# 06_ZYNQ_POWER.net
KiCad netlist of a schematic drawn in Altium Designer
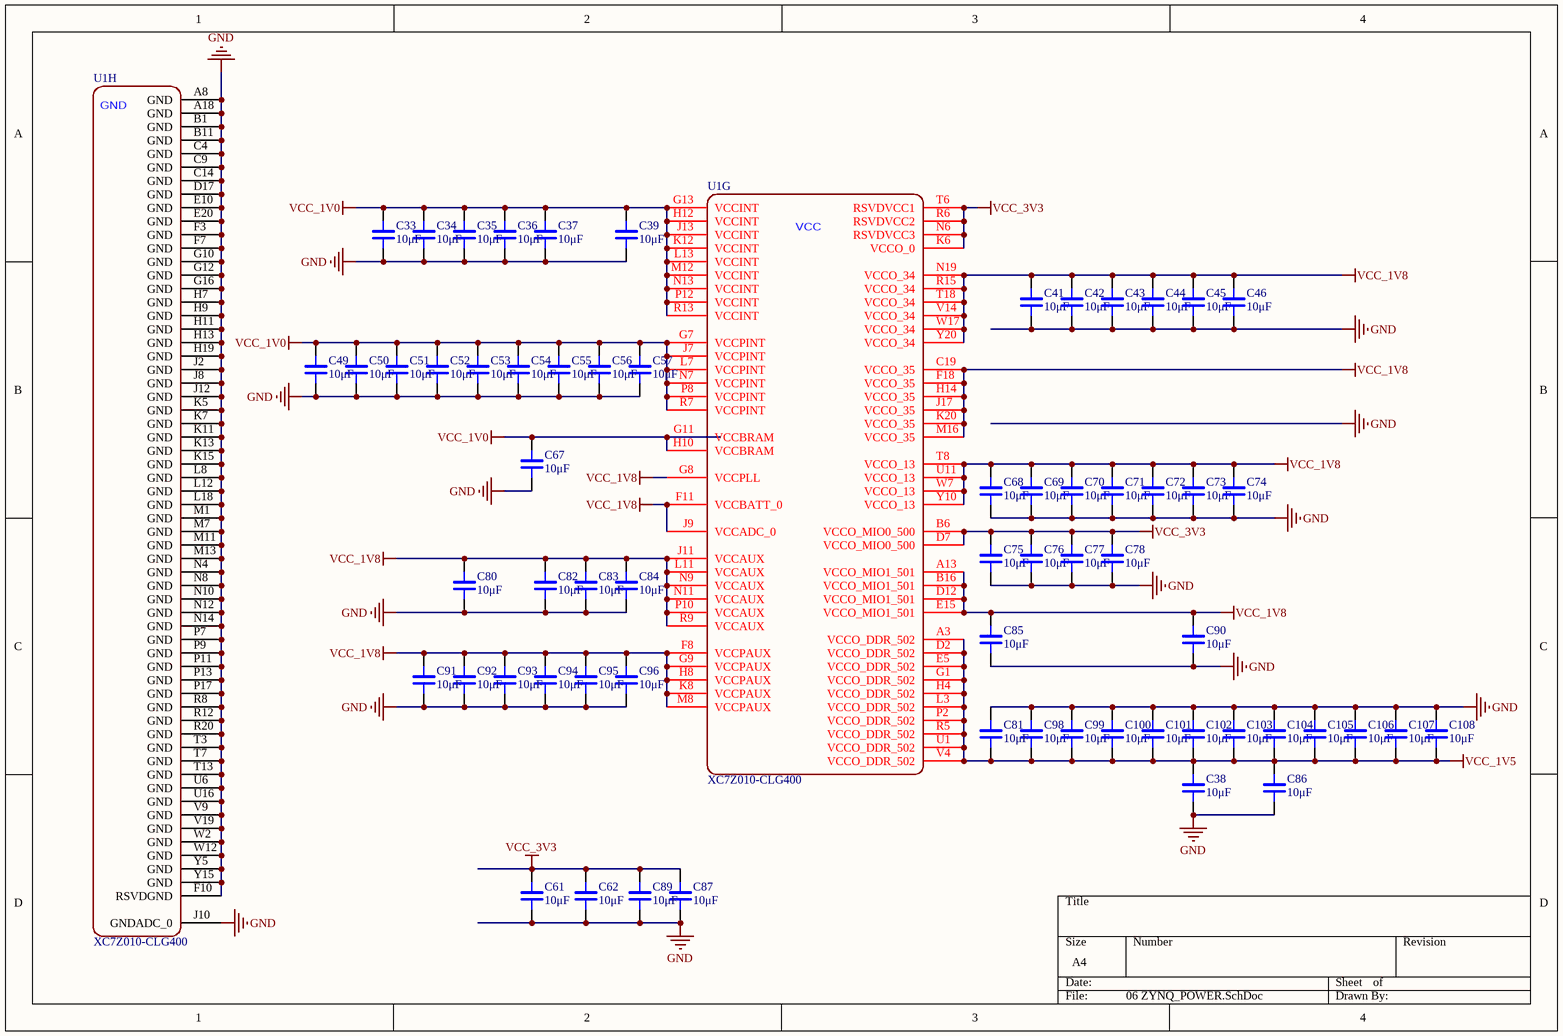
[diagram p0: 06 ZYNQ_POWER.SchDoc]

(export (version "E")
  (design (tool "Eeschema 10.0.6"))
  (components
    (comp (ref "C33")
      (value "10μF")
      (footprint "LC-0402_C")
      (description "Capacitor")
      (libsource (lib "NGFF_M_Key_xc7z010-clg400") (part "CAP_3"))
    )
    (comp (ref "C34")
      (value "10μF")
      (footprint "LC-0402_C")
      (description "Capacitor")
      (libsource (lib "NGFF_M_Key_xc7z010-clg400") (part "CAP_3"))
    )
    (comp (ref "C35")
      (value "10μF")
      (footprint "LC-0402_C")
      (description "Capacitor")
      (libsource (lib "NGFF_M_Key_xc7z010-clg400") (part "CAP_3"))
    )
    (comp (ref "C36")
      (value "10μF")
      (footprint "LC-0402_C")
      (description "Capacitor")
      (libsource (lib "NGFF_M_Key_xc7z010-clg400") (part "CAP_3"))
    )
    (comp (ref "C37")
      (value "10μF")
      (footprint "LC-0402_C")
      (description "Capacitor")
      (libsource (lib "NGFF_M_Key_xc7z010-clg400") (part "CAP_3"))
    )
    (comp (ref "C38")
      (value "10μF")
      (footprint "LC-0402_C")
      (description "Capacitor")
      (libsource (lib "NGFF_M_Key_xc7z010-clg400") (part "CAP_3"))
    )
    (comp (ref "C39")
      (value "10μF")
      (footprint "LC-0402_C")
      (description "Capacitor")
      (libsource (lib "NGFF_M_Key_xc7z010-clg400") (part "CAP_3"))
    )
    (comp (ref "C41")
      (value "10μF")
      (footprint "LC-0402_C")
      (description "Capacitor")
      (libsource (lib "NGFF_M_Key_xc7z010-clg400") (part "CAP_3"))
    )
    (comp (ref "C42")
      (value "10μF")
      (footprint "LC-0402_C")
      (description "Capacitor")
      (libsource (lib "NGFF_M_Key_xc7z010-clg400") (part "CAP_3"))
    )
    (comp (ref "C43")
      (value "10μF")
      (footprint "LC-0402_C")
      (description "Capacitor")
      (libsource (lib "NGFF_M_Key_xc7z010-clg400") (part "CAP_3"))
    )
    (comp (ref "C44")
      (value "10μF")
      (footprint "LC-0402_C")
      (description "Capacitor")
      (libsource (lib "NGFF_M_Key_xc7z010-clg400") (part "CAP_3"))
    )
    (comp (ref "C45")
      (value "10μF")
      (footprint "LC-0402_C")
      (description "Capacitor")
      (libsource (lib "NGFF_M_Key_xc7z010-clg400") (part "CAP_3"))
    )
    (comp (ref "C46")
      (value "10μF")
      (footprint "LC-0402_C")
      (description "Capacitor")
      (libsource (lib "NGFF_M_Key_xc7z010-clg400") (part "CAP_3"))
    )
    (comp (ref "C49")
      (value "10μF")
      (footprint "LC-0402_C")
      (description "Capacitor")
      (libsource (lib "NGFF_M_Key_xc7z010-clg400") (part "CAP_3"))
    )
    (comp (ref "C50")
      (value "10μF")
      (footprint "LC-0402_C")
      (description "Capacitor")
      (libsource (lib "NGFF_M_Key_xc7z010-clg400") (part "CAP_3"))
    )
    (comp (ref "C51")
      (value "10μF")
      (footprint "LC-0402_C")
      (description "Capacitor")
      (libsource (lib "NGFF_M_Key_xc7z010-clg400") (part "CAP_3"))
    )
    (comp (ref "C52")
      (value "10μF")
      (footprint "LC-0402_C")
      (description "Capacitor")
      (libsource (lib "NGFF_M_Key_xc7z010-clg400") (part "CAP_3"))
    )
    (comp (ref "C53")
      (value "10μF")
      (footprint "LC-0402_C")
      (description "Capacitor")
      (libsource (lib "NGFF_M_Key_xc7z010-clg400") (part "CAP_3"))
    )
    (comp (ref "C54")
      (value "10μF")
      (footprint "LC-0402_C")
      (description "Capacitor")
      (libsource (lib "NGFF_M_Key_xc7z010-clg400") (part "CAP_3"))
    )
    (comp (ref "C55")
      (value "10μF")
      (footprint "LC-0402_C")
      (description "Capacitor")
      (libsource (lib "NGFF_M_Key_xc7z010-clg400") (part "CAP_3"))
    )
    (comp (ref "C56")
      (value "10μF")
      (footprint "LC-0402_C")
      (description "Capacitor")
      (libsource (lib "NGFF_M_Key_xc7z010-clg400") (part "CAP_3"))
    )
    (comp (ref "C57")
      (value "10μF")
      (footprint "LC-0402_C")
      (description "Capacitor")
      (libsource (lib "NGFF_M_Key_xc7z010-clg400") (part "CAP_3"))
    )
    (comp (ref "C61")
      (value "10μF")
      (footprint "LC-0402_C")
      (description "Capacitor")
      (libsource (lib "NGFF_M_Key_xc7z010-clg400") (part "CAP_3"))
    )
    (comp (ref "C62")
      (value "10μF")
      (footprint "LC-0402_C")
      (description "Capacitor")
      (libsource (lib "NGFF_M_Key_xc7z010-clg400") (part "CAP_3"))
    )
    (comp (ref "C67")
      (value "10μF")
      (footprint "LC-0402_C")
      (description "Capacitor")
      (libsource (lib "NGFF_M_Key_xc7z010-clg400") (part "CAP_3"))
    )
    (comp (ref "C68")
      (value "10μF")
      (footprint "LC-0402_C")
      (description "Capacitor")
      (libsource (lib "NGFF_M_Key_xc7z010-clg400") (part "CAP_3"))
    )
    (comp (ref "C69")
      (value "10μF")
      (footprint "LC-0402_C")
      (description "Capacitor")
      (libsource (lib "NGFF_M_Key_xc7z010-clg400") (part "CAP_3"))
    )
    (comp (ref "C70")
      (value "10μF")
      (footprint "LC-0402_C")
      (description "Capacitor")
      (libsource (lib "NGFF_M_Key_xc7z010-clg400") (part "CAP_3"))
    )
    (comp (ref "C71")
      (value "10μF")
      (footprint "LC-0402_C")
      (description "Capacitor")
      (libsource (lib "NGFF_M_Key_xc7z010-clg400") (part "CAP_3"))
    )
    (comp (ref "C72")
      (value "10μF")
      (footprint "LC-0402_C")
      (description "Capacitor")
      (libsource (lib "NGFF_M_Key_xc7z010-clg400") (part "CAP_3"))
    )
    (comp (ref "C73")
      (value "10μF")
      (footprint "LC-0402_C")
      (description "Capacitor")
      (libsource (lib "NGFF_M_Key_xc7z010-clg400") (part "CAP_3"))
    )
    (comp (ref "C74")
      (value "10μF")
      (footprint "LC-0402_C")
      (description "Capacitor")
      (libsource (lib "NGFF_M_Key_xc7z010-clg400") (part "CAP_3"))
    )
    (comp (ref "C75")
      (value "10μF")
      (footprint "LC-0402_C")
      (description "Capacitor")
      (libsource (lib "NGFF_M_Key_xc7z010-clg400") (part "CAP_3"))
    )
    (comp (ref "C76")
      (value "10μF")
      (footprint "LC-0402_C")
      (description "Capacitor")
      (libsource (lib "NGFF_M_Key_xc7z010-clg400") (part "CAP_3"))
    )
    (comp (ref "C77")
      (value "10μF")
      (footprint "LC-0402_C")
      (description "Capacitor")
      (libsource (lib "NGFF_M_Key_xc7z010-clg400") (part "CAP_3"))
    )
    (comp (ref "C78")
      (value "10μF")
      (footprint "LC-0402_C")
      (description "Capacitor")
      (libsource (lib "NGFF_M_Key_xc7z010-clg400") (part "CAP_3"))
    )
    (comp (ref "C80")
      (value "10μF")
      (footprint "LC-0402_C")
      (description "Capacitor")
      (libsource (lib "NGFF_M_Key_xc7z010-clg400") (part "CAP_3"))
    )
    (comp (ref "C81")
      (value "10μF")
      (footprint "LC-0402_C")
      (description "Capacitor")
      (libsource (lib "NGFF_M_Key_xc7z010-clg400") (part "CAP_3"))
    )
    (comp (ref "C82")
      (value "10μF")
      (footprint "LC-0402_C")
      (description "Capacitor")
      (libsource (lib "NGFF_M_Key_xc7z010-clg400") (part "CAP_3"))
    )
    (comp (ref "C83")
      (value "10μF")
      (footprint "LC-0402_C")
      (description "Capacitor")
      (libsource (lib "NGFF_M_Key_xc7z010-clg400") (part "CAP_3"))
    )
    (comp (ref "C84")
      (value "10μF")
      (footprint "LC-0402_C")
      (description "Capacitor")
      (libsource (lib "NGFF_M_Key_xc7z010-clg400") (part "CAP_3"))
    )
    (comp (ref "C85")
      (value "10μF")
      (footprint "LC-0402_C")
      (description "Capacitor")
      (libsource (lib "NGFF_M_Key_xc7z010-clg400") (part "CAP_3"))
    )
    (comp (ref "C86")
      (value "10μF")
      (footprint "LC-0402_C")
      (description "Capacitor")
      (libsource (lib "NGFF_M_Key_xc7z010-clg400") (part "CAP_3"))
    )
    (comp (ref "C87")
      (value "10μF")
      (footprint "LC-0402_C")
      (description "Capacitor")
      (libsource (lib "NGFF_M_Key_xc7z010-clg400") (part "CAP_3"))
    )
    (comp (ref "C89")
      (value "10μF")
      (footprint "LC-0402_C")
      (description "Capacitor")
      (libsource (lib "NGFF_M_Key_xc7z010-clg400") (part "CAP_3"))
    )
    (comp (ref "C90")
      (value "10μF")
      (footprint "LC-0402_C")
      (description "Capacitor")
      (libsource (lib "NGFF_M_Key_xc7z010-clg400") (part "CAP_3"))
    )
    (comp (ref "C91")
      (value "10μF")
      (footprint "LC-0402_C")
      (description "Capacitor")
      (libsource (lib "NGFF_M_Key_xc7z010-clg400") (part "CAP_3"))
    )
    (comp (ref "C92")
      (value "10μF")
      (footprint "LC-0402_C")
      (description "Capacitor")
      (libsource (lib "NGFF_M_Key_xc7z010-clg400") (part "CAP_3"))
    )
    (comp (ref "C93")
      (value "10μF")
      (footprint "LC-0402_C")
      (description "Capacitor")
      (libsource (lib "NGFF_M_Key_xc7z010-clg400") (part "CAP_3"))
    )
    (comp (ref "C94")
      (value "10μF")
      (footprint "LC-0402_C")
      (description "Capacitor")
      (libsource (lib "NGFF_M_Key_xc7z010-clg400") (part "CAP_3"))
    )
    (comp (ref "C95")
      (value "10μF")
      (footprint "LC-0402_C")
      (description "Capacitor")
      (libsource (lib "NGFF_M_Key_xc7z010-clg400") (part "CAP_3"))
    )
    (comp (ref "C96")
      (value "10μF")
      (footprint "LC-0402_C")
      (description "Capacitor")
      (libsource (lib "NGFF_M_Key_xc7z010-clg400") (part "CAP_3"))
    )
    (comp (ref "C98")
      (value "10μF")
      (footprint "LC-0402_C")
      (description "Capacitor")
      (libsource (lib "NGFF_M_Key_xc7z010-clg400") (part "CAP_3"))
    )
    (comp (ref "C99")
      (value "10μF")
      (footprint "LC-0402_C")
      (description "Capacitor")
      (libsource (lib "NGFF_M_Key_xc7z010-clg400") (part "CAP_3"))
    )
    (comp (ref "C100")
      (value "10μF")
      (footprint "LC-0402_C")
      (description "Capacitor")
      (libsource (lib "NGFF_M_Key_xc7z010-clg400") (part "CAP_3"))
    )
    (comp (ref "C101")
      (value "10μF")
      (footprint "LC-0402_C")
      (description "Capacitor")
      (libsource (lib "NGFF_M_Key_xc7z010-clg400") (part "CAP_3"))
    )
    (comp (ref "C102")
      (value "10μF")
      (footprint "LC-0402_C")
      (description "Capacitor")
      (libsource (lib "NGFF_M_Key_xc7z010-clg400") (part "CAP_3"))
    )
    (comp (ref "C103")
      (value "10μF")
      (footprint "LC-0402_C")
      (description "Capacitor")
      (libsource (lib "NGFF_M_Key_xc7z010-clg400") (part "CAP_3"))
    )
    (comp (ref "C104")
      (value "10μF")
      (footprint "LC-0402_C")
      (description "Capacitor")
      (libsource (lib "NGFF_M_Key_xc7z010-clg400") (part "CAP_3"))
    )
    (comp (ref "C105")
      (value "10μF")
      (footprint "LC-0402_C")
      (description "Capacitor")
      (libsource (lib "NGFF_M_Key_xc7z010-clg400") (part "CAP_3"))
    )
    (comp (ref "C106")
      (value "10μF")
      (footprint "LC-0402_C")
      (description "Capacitor")
      (libsource (lib "NGFF_M_Key_xc7z010-clg400") (part "CAP_3"))
    )
    (comp (ref "C107")
      (value "10μF")
      (footprint "LC-0402_C")
      (description "Capacitor")
      (libsource (lib "NGFF_M_Key_xc7z010-clg400") (part "CAP_3"))
    )
    (comp (ref "C108")
      (value "10μF")
      (footprint "LC-0402_C")
      (description "Capacitor")
      (libsource (lib "NGFF_M_Key_xc7z010-clg400") (part "CAP_3"))
    )
    (comp (ref "U1")
      (value "XC7Z010-CLG400")
      (footprint "CLG400-0.8")
      (libsource (lib "DDR3_xc7z010-clg400") (part "XC7Z010-CLG400"))
    )
  )
  (nets
    (net (code "1") (name "GND") (class "Default")
      (node (ref "C100") (pin "2") (pinfunction "2_2") (pintype "passive"))
      (node (ref "C101") (pin "2") (pinfunction "2_2") (pintype "passive"))
      (node (ref "C102") (pin "2") (pinfunction "2_2") (pintype "passive"))
      (node (ref "C103") (pin "2") (pinfunction "2_2") (pintype "passive"))
      (node (ref "C104") (pin "2") (pinfunction "2_2") (pintype "passive"))
      (node (ref "C105") (pin "2") (pinfunction "2_2") (pintype "passive"))
      (node (ref "C106") (pin "2") (pinfunction "2_2") (pintype "passive"))
      (node (ref "C107") (pin "2") (pinfunction "2_2") (pintype "passive"))
      (node (ref "C108") (pin "2") (pinfunction "2_2") (pintype "passive"))
      (node (ref "C33") (pin "1") (pinfunction "1_1") (pintype "passive"))
      (node (ref "C34") (pin "1") (pinfunction "1_1") (pintype "passive"))
      (node (ref "C35") (pin "1") (pinfunction "1_1") (pintype "passive"))
      (node (ref "C36") (pin "1") (pinfunction "1_1") (pintype "passive"))
      (node (ref "C37") (pin "1") (pinfunction "1_1") (pintype "passive"))
      (node (ref "C38") (pin "1") (pinfunction "1_1") (pintype "passive"))
      (node (ref "C39") (pin "1") (pinfunction "1_1") (pintype "passive"))
      (node (ref "C41") (pin "1") (pinfunction "1_1") (pintype "passive"))
      (node (ref "C42") (pin "1") (pinfunction "1_1") (pintype "passive"))
      (node (ref "C43") (pin "1") (pinfunction "1_1") (pintype "passive"))
      (node (ref "C44") (pin "1") (pinfunction "1_1") (pintype "passive"))
      (node (ref "C45") (pin "1") (pinfunction "1_1") (pintype "passive"))
      (node (ref "C46") (pin "1") (pinfunction "1_1") (pintype "passive"))
      (node (ref "C49") (pin "1") (pinfunction "1_1") (pintype "passive"))
      (node (ref "C50") (pin "1") (pinfunction "1_1") (pintype "passive"))
      (node (ref "C51") (pin "1") (pinfunction "1_1") (pintype "passive"))
      (node (ref "C52") (pin "1") (pinfunction "1_1") (pintype "passive"))
      (node (ref "C53") (pin "1") (pinfunction "1_1") (pintype "passive"))
      (node (ref "C54") (pin "1") (pinfunction "1_1") (pintype "passive"))
      (node (ref "C55") (pin "1") (pinfunction "1_1") (pintype "passive"))
      (node (ref "C56") (pin "1") (pinfunction "1_1") (pintype "passive"))
      (node (ref "C57") (pin "1") (pinfunction "1_1") (pintype "passive"))
      (node (ref "C61") (pin "1") (pinfunction "1_1") (pintype "passive"))
      (node (ref "C62") (pin "1") (pinfunction "1_1") (pintype "passive"))
      (node (ref "C67") (pin "1") (pinfunction "1_1") (pintype "passive"))
      (node (ref "C68") (pin "1") (pinfunction "1_1") (pintype "passive"))
      (node (ref "C69") (pin "1") (pinfunction "1_1") (pintype "passive"))
      (node (ref "C70") (pin "1") (pinfunction "1_1") (pintype "passive"))
      (node (ref "C71") (pin "1") (pinfunction "1_1") (pintype "passive"))
      (node (ref "C72") (pin "1") (pinfunction "1_1") (pintype "passive"))
      (node (ref "C73") (pin "1") (pinfunction "1_1") (pintype "passive"))
      (node (ref "C74") (pin "1") (pinfunction "1_1") (pintype "passive"))
      (node (ref "C75") (pin "1") (pinfunction "1_1") (pintype "passive"))
      (node (ref "C76") (pin "1") (pinfunction "1_1") (pintype "passive"))
      (node (ref "C77") (pin "1") (pinfunction "1_1") (pintype "passive"))
      (node (ref "C78") (pin "1") (pinfunction "1_1") (pintype "passive"))
      (node (ref "C80") (pin "1") (pinfunction "1_1") (pintype "passive"))
      (node (ref "C81") (pin "2") (pinfunction "2_2") (pintype "passive"))
      (node (ref "C82") (pin "1") (pinfunction "1_1") (pintype "passive"))
      (node (ref "C83") (pin "1") (pinfunction "1_1") (pintype "passive"))
      (node (ref "C84") (pin "1") (pinfunction "1_1") (pintype "passive"))
      (node (ref "C85") (pin "1") (pinfunction "1_1") (pintype "passive"))
      (node (ref "C86") (pin "1") (pinfunction "1_1") (pintype "passive"))
      (node (ref "C87") (pin "1") (pinfunction "1_1") (pintype "passive"))
      (node (ref "C89") (pin "1") (pinfunction "1_1") (pintype "passive"))
      (node (ref "C90") (pin "1") (pinfunction "1_1") (pintype "passive"))
      (node (ref "C91") (pin "1") (pinfunction "1_1") (pintype "passive"))
      (node (ref "C92") (pin "1") (pinfunction "1_1") (pintype "passive"))
      (node (ref "C93") (pin "1") (pinfunction "1_1") (pintype "passive"))
      (node (ref "C94") (pin "1") (pinfunction "1_1") (pintype "passive"))
      (node (ref "C95") (pin "1") (pinfunction "1_1") (pintype "passive"))
      (node (ref "C96") (pin "1") (pinfunction "1_1") (pintype "passive"))
      (node (ref "C98") (pin "2") (pinfunction "2_2") (pintype "passive"))
      (node (ref "C99") (pin "2") (pinfunction "2_2") (pintype "passive"))
      (node (ref "U1") (pin "A18") (pinfunction "GND_A18") (pintype "passive"))
      (node (ref "U1") (pin "A8") (pinfunction "GND_A8") (pintype "passive"))
      (node (ref "U1") (pin "B1") (pinfunction "GND_B1") (pintype "passive"))
      (node (ref "U1") (pin "B11") (pinfunction "GND_B11") (pintype "passive"))
      (node (ref "U1") (pin "C14") (pinfunction "GND_C14") (pintype "passive"))
      (node (ref "U1") (pin "C4") (pinfunction "GND_C4") (pintype "passive"))
      (node (ref "U1") (pin "C9") (pinfunction "GND_C9") (pintype "passive"))
      (node (ref "U1") (pin "D17") (pinfunction "GND_D17") (pintype "passive"))
      (node (ref "U1") (pin "E10") (pinfunction "GND_E10") (pintype "passive"))
      (node (ref "U1") (pin "E20") (pinfunction "GND_E20") (pintype "passive"))
      (node (ref "U1") (pin "F10") (pinfunction "RSVDGND_F10") (pintype "passive"))
      (node (ref "U1") (pin "F3") (pinfunction "GND_F3") (pintype "passive"))
      (node (ref "U1") (pin "F7") (pinfunction "GND_F7") (pintype "passive"))
      (node (ref "U1") (pin "G10") (pinfunction "GND_G10") (pintype "passive"))
      (node (ref "U1") (pin "G12") (pinfunction "GND_G12") (pintype "passive"))
      (node (ref "U1") (pin "G16") (pinfunction "GND_G16") (pintype "passive"))
      (node (ref "U1") (pin "H11") (pinfunction "GND_H11") (pintype "passive"))
      (node (ref "U1") (pin "H13") (pinfunction "GND_H13") (pintype "passive"))
      (node (ref "U1") (pin "H19") (pinfunction "GND_H19") (pintype "passive"))
      (node (ref "U1") (pin "H7") (pinfunction "GND_H7") (pintype "passive"))
      (node (ref "U1") (pin "H9") (pinfunction "GND_H9") (pintype "passive"))
      (node (ref "U1") (pin "J10") (pinfunction "GNDADC_0_J10") (pintype "passive"))
      (node (ref "U1") (pin "J12") (pinfunction "GND_J12") (pintype "passive"))
      (node (ref "U1") (pin "J2") (pinfunction "GND_J2") (pintype "passive"))
      (node (ref "U1") (pin "J8") (pinfunction "GND_J8") (pintype "passive"))
      (node (ref "U1") (pin "K11") (pinfunction "GND_K11") (pintype "passive"))
      (node (ref "U1") (pin "K13") (pinfunction "GND_K13") (pintype "passive"))
      (node (ref "U1") (pin "K15") (pinfunction "GND_K15") (pintype "passive"))
      (node (ref "U1") (pin "K5") (pinfunction "GND_K5") (pintype "passive"))
      (node (ref "U1") (pin "K7") (pinfunction "GND_K7") (pintype "passive"))
      (node (ref "U1") (pin "L12") (pinfunction "GND_L12") (pintype "passive"))
      (node (ref "U1") (pin "L18") (pinfunction "GND_L18") (pintype "passive"))
      (node (ref "U1") (pin "L8") (pinfunction "GND_L8") (pintype "passive"))
      (node (ref "U1") (pin "M1") (pinfunction "GND_M1") (pintype "passive"))
      (node (ref "U1") (pin "M11") (pinfunction "GND_M11") (pintype "passive"))
      (node (ref "U1") (pin "M13") (pinfunction "GND_M13") (pintype "passive"))
      (node (ref "U1") (pin "M7") (pinfunction "GND_M7") (pintype "passive"))
      (node (ref "U1") (pin "N10") (pinfunction "GND_N10") (pintype "passive"))
      (node (ref "U1") (pin "N12") (pinfunction "GND_N12") (pintype "passive"))
      (node (ref "U1") (pin "N14") (pinfunction "GND_N14") (pintype "passive"))
      (node (ref "U1") (pin "N4") (pinfunction "GND_N4") (pintype "passive"))
      (node (ref "U1") (pin "N8") (pinfunction "GND_N8") (pintype "passive"))
      (node (ref "U1") (pin "P11") (pinfunction "GND_P11") (pintype "passive"))
      (node (ref "U1") (pin "P13") (pinfunction "GND_P13") (pintype "passive"))
      (node (ref "U1") (pin "P17") (pinfunction "GND_P17") (pintype "passive"))
      (node (ref "U1") (pin "P7") (pinfunction "GND_P7") (pintype "passive"))
      (node (ref "U1") (pin "P9") (pinfunction "GND_P9") (pintype "passive"))
      (node (ref "U1") (pin "R12") (pinfunction "GND_R12") (pintype "passive"))
      (node (ref "U1") (pin "R20") (pinfunction "GND_R20") (pintype "passive"))
      (node (ref "U1") (pin "R8") (pinfunction "GND_R8") (pintype "passive"))
      (node (ref "U1") (pin "T13") (pinfunction "GND_T13") (pintype "passive"))
      (node (ref "U1") (pin "T3") (pinfunction "GND_T3") (pintype "passive"))
      (node (ref "U1") (pin "T7") (pinfunction "GND_T7") (pintype "passive"))
      (node (ref "U1") (pin "U16") (pinfunction "GND_U16") (pintype "passive"))
      (node (ref "U1") (pin "U6") (pinfunction "GND_U6") (pintype "passive"))
      (node (ref "U1") (pin "V19") (pinfunction "GND_V19") (pintype "passive"))
      (node (ref "U1") (pin "V9") (pinfunction "GND_V9") (pintype "passive"))
      (node (ref "U1") (pin "W12") (pinfunction "GND_W12") (pintype "passive"))
      (node (ref "U1") (pin "W2") (pinfunction "GND_W2") (pintype "passive"))
      (node (ref "U1") (pin "Y15") (pinfunction "GND_Y15") (pintype "passive"))
      (node (ref "U1") (pin "Y5") (pinfunction "GND_Y5") (pintype "passive"))
    )
    (net (code "2") (name "VCC_1V0") (class "Default")
      (node (ref "C33") (pin "2") (pinfunction "2_2") (pintype "passive"))
      (node (ref "C34") (pin "2") (pinfunction "2_2") (pintype "passive"))
      (node (ref "C35") (pin "2") (pinfunction "2_2") (pintype "passive"))
      (node (ref "C36") (pin "2") (pinfunction "2_2") (pintype "passive"))
      (node (ref "C37") (pin "2") (pinfunction "2_2") (pintype "passive"))
      (node (ref "C39") (pin "2") (pinfunction "2_2") (pintype "passive"))
      (node (ref "C49") (pin "2") (pinfunction "2_2") (pintype "passive"))
      (node (ref "C50") (pin "2") (pinfunction "2_2") (pintype "passive"))
      (node (ref "C51") (pin "2") (pinfunction "2_2") (pintype "passive"))
      (node (ref "C52") (pin "2") (pinfunction "2_2") (pintype "passive"))
      (node (ref "C53") (pin "2") (pinfunction "2_2") (pintype "passive"))
      (node (ref "C54") (pin "2") (pinfunction "2_2") (pintype "passive"))
      (node (ref "C55") (pin "2") (pinfunction "2_2") (pintype "passive"))
      (node (ref "C56") (pin "2") (pinfunction "2_2") (pintype "passive"))
      (node (ref "C57") (pin "2") (pinfunction "2_2") (pintype "passive"))
      (node (ref "C67") (pin "2") (pinfunction "2_2") (pintype "passive"))
      (node (ref "U1") (pin "G11") (pinfunction "VCCBRAM_G11") (pintype "passive"))
      (node (ref "U1") (pin "G13") (pinfunction "VCCINT_G13") (pintype "passive"))
      (node (ref "U1") (pin "G7") (pinfunction "VCCPINT_G7") (pintype "passive"))
      (node (ref "U1") (pin "H10") (pinfunction "VCCBRAM_H10") (pintype "passive"))
      (node (ref "U1") (pin "H12") (pinfunction "VCCINT_H12") (pintype "passive"))
      (node (ref "U1") (pin "J13") (pinfunction "VCCINT_J13") (pintype "passive"))
      (node (ref "U1") (pin "J7") (pinfunction "VCCPINT_J7") (pintype "passive"))
      (node (ref "U1") (pin "K12") (pinfunction "VCCINT_K12") (pintype "passive"))
      (node (ref "U1") (pin "L13") (pinfunction "VCCINT_L13") (pintype "passive"))
      (node (ref "U1") (pin "L7") (pinfunction "VCCPINT_L7") (pintype "passive"))
      (node (ref "U1") (pin "M12") (pinfunction "VCCINT_M12") (pintype "passive"))
      (node (ref "U1") (pin "N13") (pinfunction "VCCINT_N13") (pintype "passive"))
      (node (ref "U1") (pin "N7") (pinfunction "VCCPINT_N7") (pintype "passive"))
      (node (ref "U1") (pin "P12") (pinfunction "VCCINT_P12") (pintype "passive"))
      (node (ref "U1") (pin "P8") (pinfunction "VCCPINT_P8") (pintype "passive"))
      (node (ref "U1") (pin "R13") (pinfunction "VCCINT_R13") (pintype "passive"))
      (node (ref "U1") (pin "R7") (pinfunction "VCCPINT_R7") (pintype "passive"))
    )
    (net (code "3") (name "VCC_1V5") (class "Default")
      (node (ref "C100") (pin "1") (pinfunction "1_1") (pintype "passive"))
      (node (ref "C101") (pin "1") (pinfunction "1_1") (pintype "passive"))
      (node (ref "C102") (pin "1") (pinfunction "1_1") (pintype "passive"))
      (node (ref "C103") (pin "1") (pinfunction "1_1") (pintype "passive"))
      (node (ref "C104") (pin "1") (pinfunction "1_1") (pintype "passive"))
      (node (ref "C105") (pin "1") (pinfunction "1_1") (pintype "passive"))
      (node (ref "C106") (pin "1") (pinfunction "1_1") (pintype "passive"))
      (node (ref "C107") (pin "1") (pinfunction "1_1") (pintype "passive"))
      (node (ref "C108") (pin "1") (pinfunction "1_1") (pintype "passive"))
      (node (ref "C38") (pin "2") (pinfunction "2_2") (pintype "passive"))
      (node (ref "C81") (pin "1") (pinfunction "1_1") (pintype "passive"))
      (node (ref "C86") (pin "2") (pinfunction "2_2") (pintype "passive"))
      (node (ref "C98") (pin "1") (pinfunction "1_1") (pintype "passive"))
      (node (ref "C99") (pin "1") (pinfunction "1_1") (pintype "passive"))
      (node (ref "U1") (pin "A3") (pinfunction "VCCO_DDR_502_A3") (pintype "passive"))
      (node (ref "U1") (pin "D2") (pinfunction "VCCO_DDR_502_D2") (pintype "passive"))
      (node (ref "U1") (pin "E5") (pinfunction "VCCO_DDR_502_E5") (pintype "passive"))
      (node (ref "U1") (pin "G1") (pinfunction "VCCO_DDR_502_G1") (pintype "passive"))
      (node (ref "U1") (pin "H4") (pinfunction "VCCO_DDR_502_H4") (pintype "passive"))
      (node (ref "U1") (pin "L3") (pinfunction "VCCO_DDR_502_L3") (pintype "passive"))
      (node (ref "U1") (pin "P2") (pinfunction "VCCO_DDR_502_P2") (pintype "passive"))
      (node (ref "U1") (pin "R5") (pinfunction "VCCO_DDR_502_R5") (pintype "passive"))
      (node (ref "U1") (pin "U1") (pinfunction "VCCO_DDR_502_U1") (pintype "passive"))
      (node (ref "U1") (pin "V4") (pinfunction "VCCO_DDR_502_V4") (pintype "passive"))
    )
    (net (code "4") (name "VCC_1V8") (class "Default")
      (node (ref "C41") (pin "2") (pinfunction "2_2") (pintype "passive"))
      (node (ref "C42") (pin "2") (pinfunction "2_2") (pintype "passive"))
      (node (ref "C43") (pin "2") (pinfunction "2_2") (pintype "passive"))
      (node (ref "C44") (pin "2") (pinfunction "2_2") (pintype "passive"))
      (node (ref "C45") (pin "2") (pinfunction "2_2") (pintype "passive"))
      (node (ref "C46") (pin "2") (pinfunction "2_2") (pintype "passive"))
      (node (ref "C68") (pin "2") (pinfunction "2_2") (pintype "passive"))
      (node (ref "C69") (pin "2") (pinfunction "2_2") (pintype "passive"))
      (node (ref "C70") (pin "2") (pinfunction "2_2") (pintype "passive"))
      (node (ref "C71") (pin "2") (pinfunction "2_2") (pintype "passive"))
      (node (ref "C72") (pin "2") (pinfunction "2_2") (pintype "passive"))
      (node (ref "C73") (pin "2") (pinfunction "2_2") (pintype "passive"))
      (node (ref "C74") (pin "2") (pinfunction "2_2") (pintype "passive"))
      (node (ref "C80") (pin "2") (pinfunction "2_2") (pintype "passive"))
      (node (ref "C82") (pin "2") (pinfunction "2_2") (pintype "passive"))
      (node (ref "C83") (pin "2") (pinfunction "2_2") (pintype "passive"))
      (node (ref "C84") (pin "2") (pinfunction "2_2") (pintype "passive"))
      (node (ref "C85") (pin "2") (pinfunction "2_2") (pintype "passive"))
      (node (ref "C90") (pin "2") (pinfunction "2_2") (pintype "passive"))
      (node (ref "C91") (pin "2") (pinfunction "2_2") (pintype "passive"))
      (node (ref "C92") (pin "2") (pinfunction "2_2") (pintype "passive"))
      (node (ref "C93") (pin "2") (pinfunction "2_2") (pintype "passive"))
      (node (ref "C94") (pin "2") (pinfunction "2_2") (pintype "passive"))
      (node (ref "C95") (pin "2") (pinfunction "2_2") (pintype "passive"))
      (node (ref "C96") (pin "2") (pinfunction "2_2") (pintype "passive"))
      (node (ref "U1") (pin "A13") (pinfunction "VCCO_MIO1_501_A13") (pintype "passive"))
      (node (ref "U1") (pin "B16") (pinfunction "VCCO_MIO1_501_B16") (pintype "passive"))
      (node (ref "U1") (pin "C19") (pinfunction "VCCO_35_C19") (pintype "passive"))
      (node (ref "U1") (pin "D12") (pinfunction "VCCO_MIO1_501_D12") (pintype "passive"))
      (node (ref "U1") (pin "E15") (pinfunction "VCCO_MIO1_501_E15") (pintype "passive"))
      (node (ref "U1") (pin "F11") (pinfunction "VCCBATT_0_F11") (pintype "passive"))
      (node (ref "U1") (pin "F18") (pinfunction "VCCO_35_F18") (pintype "passive"))
      (node (ref "U1") (pin "F8") (pinfunction "VCCPAUX_F8") (pintype "passive"))
      (node (ref "U1") (pin "G8") (pinfunction "VCCPLL_G8") (pintype "passive"))
      (node (ref "U1") (pin "G9") (pinfunction "VCCPAUX_G9") (pintype "passive"))
      (node (ref "U1") (pin "H14") (pinfunction "VCCO_35_H14") (pintype "passive"))
      (node (ref "U1") (pin "H8") (pinfunction "VCCPAUX_H8") (pintype "passive"))
      (node (ref "U1") (pin "J11") (pinfunction "VCCAUX_J11") (pintype "passive"))
      (node (ref "U1") (pin "J17") (pinfunction "VCCO_35_J17") (pintype "passive"))
      (node (ref "U1") (pin "J9") (pinfunction "VCCADC_0_J9") (pintype "passive"))
      (node (ref "U1") (pin "K20") (pinfunction "VCCO_35_K20") (pintype "passive"))
      (node (ref "U1") (pin "K8") (pinfunction "VCCPAUX_K8") (pintype "passive"))
      (node (ref "U1") (pin "L11") (pinfunction "VCCAUX_L11") (pintype "passive"))
      (node (ref "U1") (pin "M16") (pinfunction "VCCO_35_M16") (pintype "passive"))
      (node (ref "U1") (pin "M8") (pinfunction "VCCPAUX_M8") (pintype "passive"))
      (node (ref "U1") (pin "N11") (pinfunction "VCCAUX_N11") (pintype "passive"))
      (node (ref "U1") (pin "N19") (pinfunction "VCCO_34_N19") (pintype "passive"))
      (node (ref "U1") (pin "N9") (pinfunction "VCCAUX_N9") (pintype "passive"))
      (node (ref "U1") (pin "P10") (pinfunction "VCCAUX_P10") (pintype "passive"))
      (node (ref "U1") (pin "R15") (pinfunction "VCCO_34_R15") (pintype "passive"))
      (node (ref "U1") (pin "R9") (pinfunction "VCCAUX_R9") (pintype "passive"))
      (node (ref "U1") (pin "T18") (pinfunction "VCCO_34_T18") (pintype "passive"))
      (node (ref "U1") (pin "T8") (pinfunction "VCCO_13_T8") (pintype "passive"))
      (node (ref "U1") (pin "U11") (pinfunction "VCCO_13_U11") (pintype "passive"))
      (node (ref "U1") (pin "V14") (pinfunction "VCCO_34_V14") (pintype "passive"))
      (node (ref "U1") (pin "W17") (pinfunction "VCCO_34_W17") (pintype "passive"))
      (node (ref "U1") (pin "W7") (pinfunction "VCCO_13_W7") (pintype "passive"))
      (node (ref "U1") (pin "Y10") (pinfunction "VCCO_13_Y10") (pintype "passive"))
      (node (ref "U1") (pin "Y20") (pinfunction "VCCO_34_Y20") (pintype "passive"))
    )
    (net (code "5") (name "VCC_3V3") (class "Default")
      (node (ref "C61") (pin "2") (pinfunction "2_2") (pintype "passive"))
      (node (ref "C62") (pin "2") (pinfunction "2_2") (pintype "passive"))
      (node (ref "C75") (pin "2") (pinfunction "2_2") (pintype "passive"))
      (node (ref "C76") (pin "2") (pinfunction "2_2") (pintype "passive"))
      (node (ref "C77") (pin "2") (pinfunction "2_2") (pintype "passive"))
      (node (ref "C78") (pin "2") (pinfunction "2_2") (pintype "passive"))
      (node (ref "C87") (pin "2") (pinfunction "2_2") (pintype "passive"))
      (node (ref "C89") (pin "2") (pinfunction "2_2") (pintype "passive"))
      (node (ref "U1") (pin "B6") (pinfunction "VCCO_MIO0_500_B6") (pintype "passive"))
      (node (ref "U1") (pin "D7") (pinfunction "VCCO_MIO0_500_D7") (pintype "passive"))
      (node (ref "U1") (pin "K6") (pinfunction "VCCO_0_K6") (pintype "passive"))
      (node (ref "U1") (pin "N6") (pinfunction "RSVDVCC3_N6") (pintype "passive"))
      (node (ref "U1") (pin "R6") (pinfunction "RSVDVCC2_R6") (pintype "passive"))
      (node (ref "U1") (pin "T6") (pinfunction "RSVDVCC1_T6") (pintype "passive"))
    )
  )
)
